# DispBat.net
KiCad netlist of a schematic drawn in EAGLE
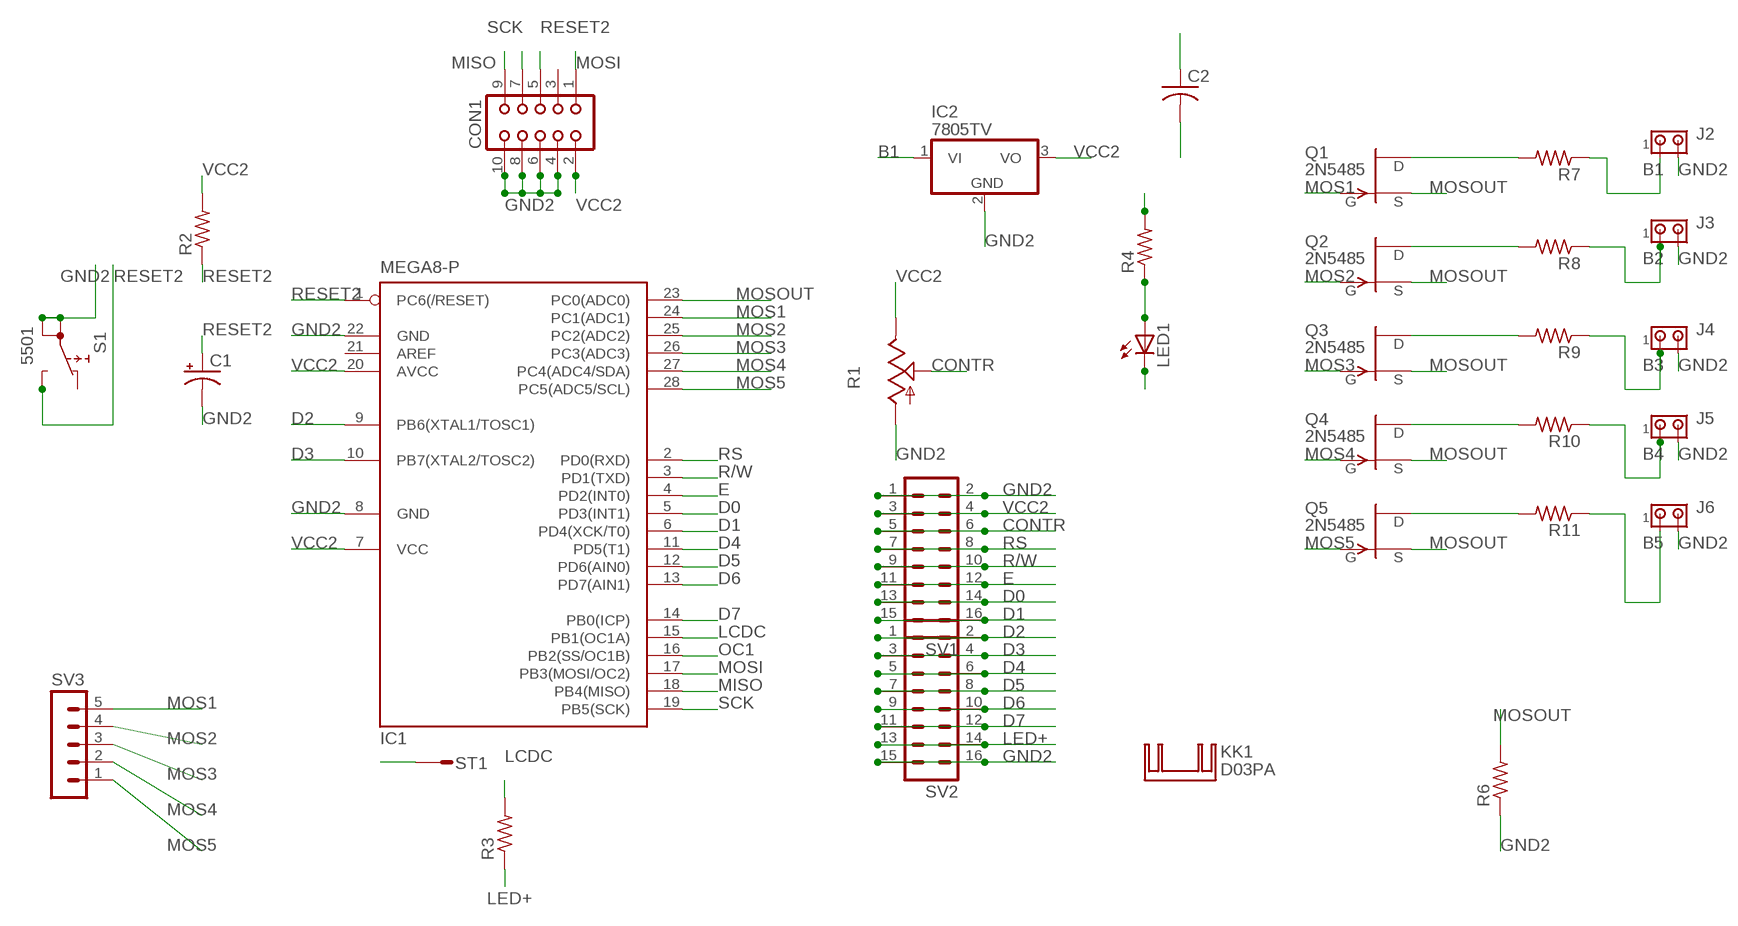
[diagram p0: schematic, sheet 1]

(export (version "E")
  (design (tool "Eeschema 10.0.6"))
  (components
    (comp (ref "C1")
      (value "CPOL-USE2.5-7")
      (footprint "eagle-import:E2,5-7")
      (libsource (lib "eagle-import") (part "CPOL-USE2.5-7"))
    )
    (comp (ref "C2")
      (value "C-US075-042X103")
      (footprint "eagle-import:C075-042X103")
      (libsource (lib "eagle-import") (part "C-US075-042X103"))
    )
    (comp (ref "CON1")
      (value "CON10")
      (footprint "eagle-import:CON10")
      (libsource (lib "eagle-import") (part "CON10"))
    )
    (comp (ref "IC1")
      (value "MEGA8-P")
      (footprint "eagle-import:DIL28-3")
      (libsource (lib "eagle-import") (part "MEGA8-P"))
    )
    (comp (ref "IC2")
      (value "7805TV")
      (footprint "eagle-import:TO220V")
      (libsource (lib "eagle-import") (part "78TV05"))
    )
    (comp (ref "J2")
      (value "MTA02-156")
      (footprint "eagle-import:1X2MTA")
      (libsource (lib "eagle-import") (part "MTA02-156"))
    )
    (comp (ref "J3")
      (value "MTA02-156")
      (footprint "eagle-import:1X2MTA")
      (libsource (lib "eagle-import") (part "MTA02-156"))
    )
    (comp (ref "J4")
      (value "MTA02-156")
      (footprint "eagle-import:1X2MTA")
      (libsource (lib "eagle-import") (part "MTA02-156"))
    )
    (comp (ref "J5")
      (value "MTA02-156")
      (footprint "eagle-import:1X2MTA")
      (libsource (lib "eagle-import") (part "MTA02-156"))
    )
    (comp (ref "J6")
      (value "MTA02-156")
      (footprint "eagle-import:1X2MTA")
      (libsource (lib "eagle-import") (part "MTA02-156"))
    )
    (comp (ref "KK1")
      (value "D03PA")
      (footprint "eagle-import:D03PA")
      (libsource (lib "eagle-import") (part "D03PA"))
    )
    (comp (ref "LED1")
      (value "LED_ELD260")
      (footprint "eagle-import:LED_LD260")
      (libsource (lib "eagle-import") (part "LED_ELD260"))
    )
    (comp (ref "Q1")
      (value "2N5485")
      (footprint "eagle-import:TO92-")
      (libsource (lib "eagle-import") (part "?5482N5"))
    )
    (comp (ref "Q2")
      (value "2N5485")
      (footprint "eagle-import:TO92-")
      (libsource (lib "eagle-import") (part "?5482N5"))
    )
    (comp (ref "Q3")
      (value "2N5485")
      (footprint "eagle-import:TO92-")
      (libsource (lib "eagle-import") (part "?5482N5"))
    )
    (comp (ref "Q4")
      (value "2N5485")
      (footprint "eagle-import:TO92-")
      (libsource (lib "eagle-import") (part "?5482N5"))
    )
    (comp (ref "Q5")
      (value "2N5485")
      (footprint "eagle-import:TO92-")
      (libsource (lib "eagle-import") (part "?5482N5"))
    )
    (comp (ref "R1")
      (value "TRIM_US-CA9V")
      (footprint "eagle-import:CA9V")
      (libsource (lib "eagle-import") (part "TRIM_US-CA9V"))
    )
    (comp (ref "R2")
      (value "R-US_0207/10")
      (footprint "eagle-import:0207_10")
      (libsource (lib "eagle-import") (part "R-US_0207/10"))
    )
    (comp (ref "R3")
      (value "R-US_0207/10")
      (footprint "eagle-import:0207_10")
      (libsource (lib "eagle-import") (part "R-US_0207/10"))
    )
    (comp (ref "R4")
      (value "R-US_0207/10")
      (footprint "eagle-import:0207_10")
      (libsource (lib "eagle-import") (part "R-US_0207/10"))
    )
    (comp (ref "R6")
      (value "R-US_0207/10")
      (footprint "eagle-import:0207_10")
      (libsource (lib "eagle-import") (part "R-US_0207/10"))
    )
    (comp (ref "R7")
      (value "R-US_0207/10")
      (footprint "eagle-import:0207_10")
      (libsource (lib "eagle-import") (part "R-US_0207/10"))
    )
    (comp (ref "R8")
      (value "R-US_0207/10")
      (footprint "eagle-import:0207_10")
      (libsource (lib "eagle-import") (part "R-US_0207/10"))
    )
    (comp (ref "R9")
      (value "R-US_0207/10")
      (footprint "eagle-import:0207_10")
      (libsource (lib "eagle-import") (part "R-US_0207/10"))
    )
    (comp (ref "R10")
      (value "R-US_0207/10")
      (footprint "eagle-import:0207_10")
      (libsource (lib "eagle-import") (part "R-US_0207/10"))
    )
    (comp (ref "R11")
      (value "R-US_0207/10")
      (footprint "eagle-import:0207_10")
      (libsource (lib "eagle-import") (part "R-US_0207/10"))
    )
    (comp (ref "S1")
      (value "5501")
      (footprint "eagle-import:5501")
      (libsource (lib "eagle-import") (part "55?01"))
    )
    (comp (ref "ST1")
      (value "ST2,8")
      (footprint "eagle-import:ST2,8")
      (libsource (lib "eagle-import") (part "ST2,8"))
    )
    (comp (ref "SV1")
      (value "MA08-2")
      (footprint "eagle-import:MA08-2")
      (libsource (lib "eagle-import") (part "MA08-2"))
    )
    (comp (ref "SV2")
      (value "MA08-2")
      (footprint "eagle-import:MA08-2")
      (libsource (lib "eagle-import") (part "MA08-2"))
    )
    (comp (ref "SV3")
      (value "MA05-1")
      (footprint "eagle-import:MA05-1")
      (libsource (lib "eagle-import") (part "MA05-1"))
    )
  )
  (nets
    (net (code "1") (name "/B1") (class "Default")
      (node (ref "IC2") (pin "1") (pinfunction "VI_1") (pintype "input"))
      (node (ref "J2") (pin "1") (pinfunction "1_1") (pintype "passive"))
      (node (ref "R7") (pin "1") (pinfunction "1_1") (pintype "passive"))
    )
    (net (code "2") (name "/B2") (class "Default")
      (node (ref "J3") (pin "1") (pinfunction "1_1") (pintype "passive"))
      (node (ref "R8") (pin "1") (pinfunction "1_1") (pintype "passive"))
    )
    (net (code "3") (name "/B3") (class "Default")
      (node (ref "J4") (pin "1") (pinfunction "1_1") (pintype "passive"))
      (node (ref "R9") (pin "1") (pinfunction "1_1") (pintype "passive"))
    )
    (net (code "4") (name "/B4") (class "Default")
      (node (ref "J5") (pin "1") (pinfunction "1_1") (pintype "passive"))
      (node (ref "R10") (pin "1") (pinfunction "1_1") (pintype "passive"))
    )
    (net (code "5") (name "/B5") (class "Default")
      (node (ref "J6") (pin "1") (pinfunction "1_1") (pintype "passive"))
      (node (ref "R11") (pin "1") (pinfunction "1_1") (pintype "passive"))
    )
    (net (code "6") (name "/CONTR") (class "Default")
      (node (ref "R1") (pin "S") (pinfunction "S_S") (pintype "passive"))
      (node (ref "SV1") (pin "5") (pinfunction "5_5") (pintype "passive"))
      (node (ref "SV1") (pin "6") (pinfunction "6_6") (pintype "passive"))
    )
    (net (code "7") (name "/D0") (class "Default")
      (node (ref "IC1") (pin "5") (pinfunction "PD3(INT1)_5") (pintype "bidirectional"))
      (node (ref "SV1") (pin "13") (pinfunction "13_13") (pintype "passive"))
      (node (ref "SV1") (pin "14") (pinfunction "14_14") (pintype "passive"))
    )
    (net (code "8") (name "/D1") (class "Default")
      (node (ref "IC1") (pin "6") (pinfunction "PD4(XCK/T0)_6") (pintype "bidirectional"))
      (node (ref "SV1") (pin "15") (pinfunction "15_15") (pintype "passive"))
      (node (ref "SV1") (pin "16") (pinfunction "16_16") (pintype "passive"))
    )
    (net (code "9") (name "/D2") (class "Default")
      (node (ref "IC1") (pin "9") (pinfunction "PB6(XTAL1/TOSC1)_9") (pintype "bidirectional"))
      (node (ref "SV2") (pin "1") (pinfunction "1_1") (pintype "passive"))
      (node (ref "SV2") (pin "2") (pinfunction "2_2") (pintype "passive"))
    )
    (net (code "10") (name "/D3") (class "Default")
      (node (ref "IC1") (pin "10") (pinfunction "PB7(XTAL2/TOSC2)_10") (pintype "bidirectional"))
      (node (ref "SV2") (pin "3") (pinfunction "3_3") (pintype "passive"))
      (node (ref "SV2") (pin "4") (pinfunction "4_4") (pintype "passive"))
    )
    (net (code "11") (name "/D4") (class "Default")
      (node (ref "IC1") (pin "11") (pinfunction "PD5(T1)_11") (pintype "bidirectional"))
      (node (ref "SV2") (pin "5") (pinfunction "5_5") (pintype "passive"))
      (node (ref "SV2") (pin "6") (pinfunction "6_6") (pintype "passive"))
    )
    (net (code "12") (name "/D5") (class "Default")
      (node (ref "IC1") (pin "12") (pinfunction "PD6(AIN0)_12") (pintype "bidirectional"))
      (node (ref "SV2") (pin "7") (pinfunction "7_7") (pintype "passive"))
      (node (ref "SV2") (pin "8") (pinfunction "8_8") (pintype "passive"))
    )
    (net (code "13") (name "/D6") (class "Default")
      (node (ref "IC1") (pin "13") (pinfunction "PD7(AIN1)_13") (pintype "bidirectional"))
      (node (ref "SV2") (pin "10") (pinfunction "10_10") (pintype "passive"))
      (node (ref "SV2") (pin "9") (pinfunction "9_9") (pintype "passive"))
    )
    (net (code "14") (name "/D7") (class "Default")
      (node (ref "IC1") (pin "14") (pinfunction "PB0(ICP)_14") (pintype "bidirectional"))
      (node (ref "SV2") (pin "11") (pinfunction "11_11") (pintype "passive"))
      (node (ref "SV2") (pin "12") (pinfunction "12_12") (pintype "passive"))
    )
    (net (code "15") (name "/E") (class "Default")
      (node (ref "IC1") (pin "4") (pinfunction "PD2(INT0)_4") (pintype "bidirectional"))
      (node (ref "SV1") (pin "11") (pinfunction "11_11") (pintype "passive"))
      (node (ref "SV1") (pin "12") (pinfunction "12_12") (pintype "passive"))
    )
    (net (code "16") (name "/GND2") (class "Default")
      (node (ref "C1") (pin "-") (pinfunction "-_-") (pintype "passive"))
      (node (ref "C2") (pin "2") (pinfunction "2_2") (pintype "passive"))
      (node (ref "CON1") (pin "10") (pinfunction "10_10") (pintype "passive"))
      (node (ref "CON1") (pin "4") (pinfunction "4_4") (pintype "passive"))
      (node (ref "CON1") (pin "6") (pinfunction "6_6") (pintype "passive"))
      (node (ref "CON1") (pin "8") (pinfunction "8_8") (pintype "passive"))
      (node (ref "IC1") (pin "22") (pinfunction "GND_22") (pintype "power_in"))
      (node (ref "IC1") (pin "8") (pinfunction "GND_8") (pintype "power_in"))
      (node (ref "IC2") (pin "2") (pinfunction "GND_2") (pintype "passive"))
      (node (ref "J2") (pin "2") (pinfunction "2_2") (pintype "passive"))
      (node (ref "J3") (pin "2") (pinfunction "2_2") (pintype "passive"))
      (node (ref "J4") (pin "2") (pinfunction "2_2") (pintype "passive"))
      (node (ref "J5") (pin "2") (pinfunction "2_2") (pintype "passive"))
      (node (ref "J6") (pin "2") (pinfunction "2_2") (pintype "passive"))
      (node (ref "LED1") (pin "K") (pinfunction "C_K") (pintype "passive"))
      (node (ref "R1") (pin "A") (pinfunction "A_A") (pintype "passive"))
      (node (ref "R6") (pin "1") (pinfunction "1_1") (pintype "passive"))
      (node (ref "S1") (pin "1A") (pinfunction "1A_1A") (pintype "passive"))
      (node (ref "S1") (pin "1B") (pinfunction "1B_1B") (pintype "passive"))
      (node (ref "SV1") (pin "1") (pinfunction "1_1") (pintype "passive"))
      (node (ref "SV1") (pin "2") (pinfunction "2_2") (pintype "passive"))
      (node (ref "SV2") (pin "15") (pinfunction "15_15") (pintype "passive"))
      (node (ref "SV2") (pin "16") (pinfunction "16_16") (pintype "passive"))
    )
    (net (code "17") (name "/LCDC") (class "Default")
      (node (ref "IC1") (pin "15") (pinfunction "PB1(OC1A)_15") (pintype "bidirectional"))
      (node (ref "R3") (pin "2") (pinfunction "2_2") (pintype "passive"))
    )
    (net (code "18") (name "/LED+") (class "Default")
      (node (ref "R3") (pin "1") (pinfunction "1_1") (pintype "passive"))
      (node (ref "SV2") (pin "13") (pinfunction "13_13") (pintype "passive"))
      (node (ref "SV2") (pin "14") (pinfunction "14_14") (pintype "passive"))
    )
    (net (code "19") (name "/MISO") (class "Default")
      (node (ref "CON1") (pin "9") (pinfunction "9_9") (pintype "passive"))
      (node (ref "IC1") (pin "18") (pinfunction "PB4(MISO)_18") (pintype "bidirectional"))
    )
    (net (code "20") (name "/MOS1") (class "Default")
      (node (ref "IC1") (pin "24") (pinfunction "PC1(ADC1)_24") (pintype "bidirectional"))
      (node (ref "Q1") (pin "1") (pinfunction "G_1") (pintype "passive"))
      (node (ref "SV3") (pin "5") (pinfunction "5_5") (pintype "passive"))
    )
    (net (code "21") (name "/MOS2") (class "Default")
      (node (ref "IC1") (pin "25") (pinfunction "PC2(ADC2)_25") (pintype "bidirectional"))
      (node (ref "Q2") (pin "1") (pinfunction "G_1") (pintype "passive"))
      (node (ref "SV3") (pin "4") (pinfunction "4_4") (pintype "passive"))
    )
    (net (code "22") (name "/MOS3") (class "Default")
      (node (ref "IC1") (pin "26") (pinfunction "PC3(ADC3)_26") (pintype "bidirectional"))
      (node (ref "Q3") (pin "1") (pinfunction "G_1") (pintype "passive"))
      (node (ref "SV3") (pin "3") (pinfunction "3_3") (pintype "passive"))
    )
    (net (code "23") (name "/MOS4") (class "Default")
      (node (ref "IC1") (pin "27") (pinfunction "PC4(ADC4/SDA)_27") (pintype "bidirectional"))
      (node (ref "Q4") (pin "1") (pinfunction "G_1") (pintype "passive"))
      (node (ref "SV3") (pin "2") (pinfunction "2_2") (pintype "passive"))
    )
    (net (code "24") (name "/MOS5") (class "Default")
      (node (ref "IC1") (pin "28") (pinfunction "PC5(ADC5/SCL)_28") (pintype "bidirectional"))
      (node (ref "Q5") (pin "1") (pinfunction "G_1") (pintype "passive"))
      (node (ref "SV3") (pin "1") (pinfunction "1_1") (pintype "passive"))
    )
    (net (code "25") (name "/MOSI") (class "Default")
      (node (ref "CON1") (pin "1") (pinfunction "1_1") (pintype "passive"))
      (node (ref "IC1") (pin "17") (pinfunction "PB3(MOSI/OC2)_17") (pintype "bidirectional"))
    )
    (net (code "26") (name "/MOSOUT") (class "Default")
      (node (ref "IC1") (pin "23") (pinfunction "PC0(ADC0)_23") (pintype "bidirectional"))
      (node (ref "Q1") (pin "2") (pinfunction "S_2") (pintype "passive"))
      (node (ref "Q2") (pin "2") (pinfunction "S_2") (pintype "passive"))
      (node (ref "Q3") (pin "2") (pinfunction "S_2") (pintype "passive"))
      (node (ref "Q4") (pin "2") (pinfunction "S_2") (pintype "passive"))
      (node (ref "Q5") (pin "2") (pinfunction "S_2") (pintype "passive"))
      (node (ref "R6") (pin "2") (pinfunction "2_2") (pintype "passive"))
    )
    (net (code "27") (name "/OC1") (class "Default")
      (node (ref "IC1") (pin "16") (pinfunction "PB2(SS/OC1B)_16") (pintype "bidirectional"))
      (node (ref "ST1") (pin "1") (pinfunction "ST_1") (pintype "passive"))
    )
    (net (code "28") (name "/RESET2") (class "Default")
      (node (ref "C1") (pin "+") (pinfunction "+_+") (pintype "passive"))
      (node (ref "CON1") (pin "5") (pinfunction "5_5") (pintype "passive"))
      (node (ref "IC1") (pin "1") (pinfunction "PC6(/RESET)_1") (pintype "bidirectional"))
      (node (ref "R2") (pin "1") (pinfunction "1_1") (pintype "passive"))
      (node (ref "S1") (pin "NO") (pinfunction "NO_NO") (pintype "passive"))
    )
    (net (code "29") (name "/RS") (class "Default")
      (node (ref "IC1") (pin "2") (pinfunction "PD0(RXD)_2") (pintype "bidirectional"))
      (node (ref "SV1") (pin "7") (pinfunction "7_7") (pintype "passive"))
      (node (ref "SV1") (pin "8") (pinfunction "8_8") (pintype "passive"))
    )
    (net (code "30") (name "/R{slash}W") (class "Default")
      (node (ref "IC1") (pin "3") (pinfunction "PD1(TXD)_3") (pintype "bidirectional"))
      (node (ref "SV1") (pin "10") (pinfunction "10_10") (pintype "passive"))
      (node (ref "SV1") (pin "9") (pinfunction "9_9") (pintype "passive"))
    )
    (net (code "31") (name "/SCK") (class "Default")
      (node (ref "CON1") (pin "7") (pinfunction "7_7") (pintype "passive"))
      (node (ref "IC1") (pin "19") (pinfunction "PB5(SCK)_19") (pintype "bidirectional"))
    )
    (net (code "32") (name "/VCC2") (class "Default")
      (node (ref "C2") (pin "1") (pinfunction "1_1") (pintype "passive"))
      (node (ref "CON1") (pin "2") (pinfunction "2_2") (pintype "passive"))
      (node (ref "IC1") (pin "20") (pinfunction "AVCC_20") (pintype "power_in"))
      (node (ref "IC1") (pin "7") (pinfunction "VCC_7") (pintype "power_in"))
      (node (ref "IC2") (pin "3") (pinfunction "VO_3") (pintype "passive"))
      (node (ref "R1") (pin "E") (pinfunction "E_E") (pintype "passive"))
      (node (ref "R2") (pin "2") (pinfunction "2_2") (pintype "passive"))
      (node (ref "R4") (pin "2") (pinfunction "2_2") (pintype "passive"))
      (node (ref "SV1") (pin "3") (pinfunction "3_3") (pintype "passive"))
      (node (ref "SV1") (pin "4") (pinfunction "4_4") (pintype "passive"))
    )
    (net (code "33") (name "Net-(LED1-PadA)") (class "Default")
      (node (ref "LED1") (pin "A") (pinfunction "A_A") (pintype "passive"))
      (node (ref "R4") (pin "1") (pinfunction "1_1") (pintype "passive"))
    )
    (net (code "34") (name "Net-(Q1-D)") (class "Default")
      (node (ref "Q1") (pin "3") (pinfunction "D_3") (pintype "passive"))
      (node (ref "R7") (pin "2") (pinfunction "2_2") (pintype "passive"))
    )
    (net (code "35") (name "Net-(Q2-D)") (class "Default")
      (node (ref "Q2") (pin "3") (pinfunction "D_3") (pintype "passive"))
      (node (ref "R8") (pin "2") (pinfunction "2_2") (pintype "passive"))
    )
    (net (code "36") (name "Net-(Q3-D)") (class "Default")
      (node (ref "Q3") (pin "3") (pinfunction "D_3") (pintype "passive"))
      (node (ref "R9") (pin "2") (pinfunction "2_2") (pintype "passive"))
    )
    (net (code "37") (name "Net-(Q4-D)") (class "Default")
      (node (ref "Q4") (pin "3") (pinfunction "D_3") (pintype "passive"))
      (node (ref "R10") (pin "2") (pinfunction "2_2") (pintype "passive"))
    )
    (net (code "38") (name "Net-(Q5-D)") (class "Default")
      (node (ref "Q5") (pin "3") (pinfunction "D_3") (pintype "passive"))
      (node (ref "R11") (pin "2") (pinfunction "2_2") (pintype "passive"))
    )
    (net (code "39") (name "unconnected-(CON1-Pad3)") (class "Default")
      (node (ref "CON1") (pin "3") (pinfunction "3_3") (pintype "passive"))
    )
    (net (code "40") (name "unconnected-(IC1-AREF-Pad21)") (class "Default")
      (node (ref "IC1") (pin "21") (pinfunction "AREF_21") (pintype "passive"))
    )
    (net (code "41") (name "unconnected-(S1-PadNC)") (class "Default")
      (node (ref "S1") (pin "NC") (pinfunction "NC_NC") (pintype "passive"))
    )
  )
)
